# Stratologger_sl100_Board.net
KiCad netlist of a schematic drawn in EAGLE
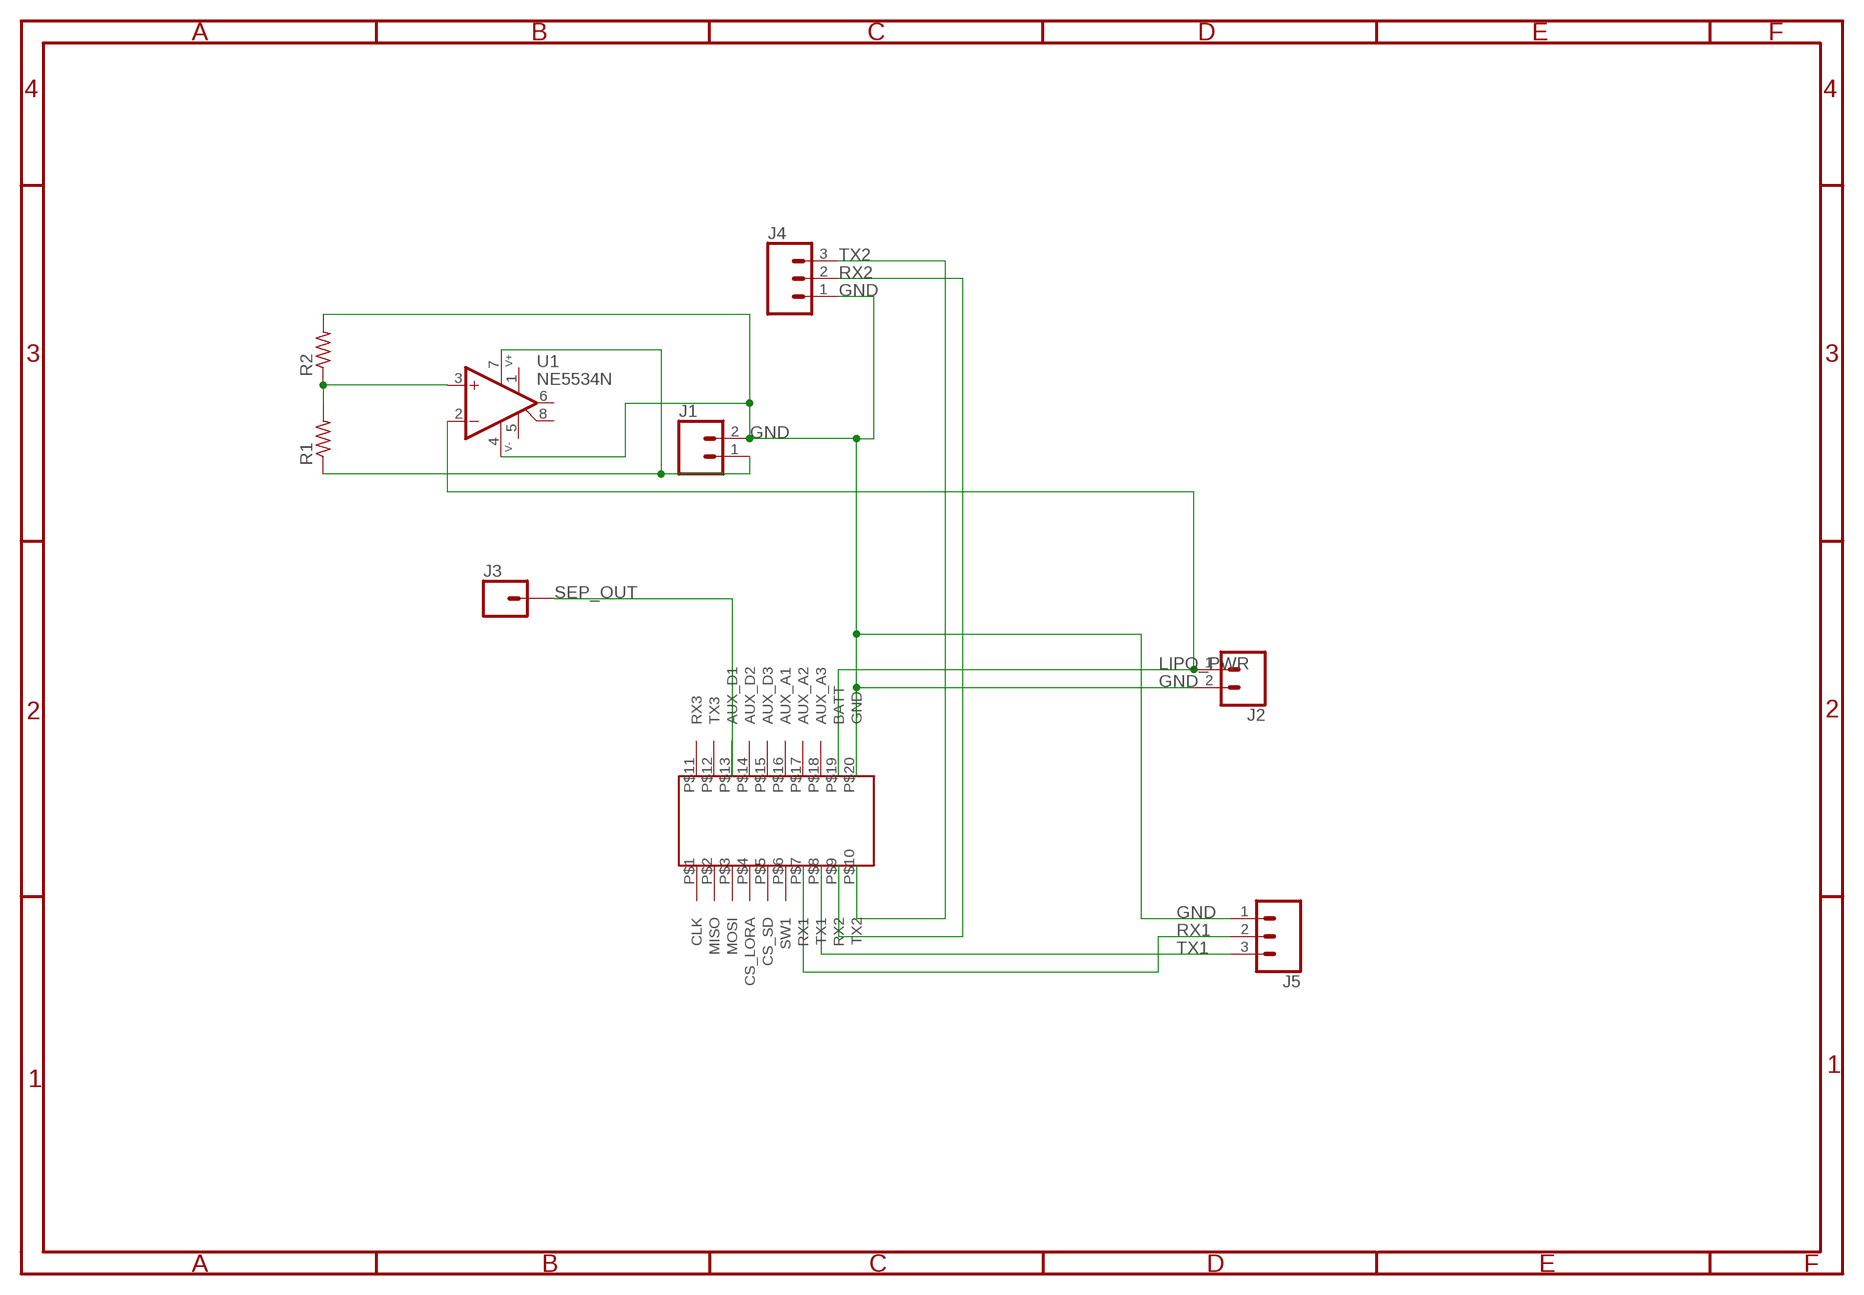
[diagram p0: schematic, sheet 1]

(export (version "E")
  (design (tool "Eeschema 10.0.6"))
  (components
    (comp (ref "J1")
      (value "CONN_02")
      (footprint "eagle-import:1X02")
      (libsource (lib "eagle-import") (part "CONN_02"))
    )
    (comp (ref "J2")
      (value "CONN_02")
      (footprint "eagle-import:1X02")
      (libsource (lib "eagle-import") (part "CONN_02"))
    )
    (comp (ref "J3")
      (value "CONN_01")
      (footprint "eagle-import:1X01")
      (libsource (lib "eagle-import") (part "CONN_01"))
    )
    (comp (ref "J4")
      (value "CONN_03")
      (footprint "eagle-import:1X03")
      (libsource (lib "eagle-import") (part "CONN_03"))
    )
    (comp (ref "J5")
      (value "CONN_03")
      (footprint "eagle-import:1X03")
      (libsource (lib "eagle-import") (part "CONN_03"))
    )
    (comp (ref "R1")
      (value "R-US_0207/12")
      (footprint "eagle-import:0207_12")
      (libsource (lib "eagle-import") (part "R-US_0207/12"))
    )
    (comp (ref "R2")
      (value "R-US_0207/12")
      (footprint "eagle-import:0207_12")
      (libsource (lib "eagle-import") (part "R-US_0207/12"))
    )
    (comp (ref "U$2")
      (value "STRATOLOGGER")
      (footprint "eagle-import:STRATOLOGGER")
      (libsource (lib "eagle-import") (part "STRATOLOGGER"))
    )
    (comp (ref "U$3")
      (value "SMALLHEADERPACKAGE")
      (footprint "eagle-import:SMALLHEADERPACKAGE")
      (libsource (lib "eagle-import") (part "SMALLHEADERPACKAGE"))
    )
    (comp (ref "U1")
      (value "NE5534N")
      (footprint "eagle-import:DIL08")
      (libsource (lib "eagle-import") (part "NE5534N"))
    )
  )
  (nets
    (net (code "1") (name "/GND") (class "Default")
      (node (ref "J1") (pin "2") (pinfunction "2_2") (pintype "passive"))
      (node (ref "J2") (pin "2") (pinfunction "2_2") (pintype "passive"))
      (node (ref "J4") (pin "1") (pinfunction "1_1") (pintype "passive"))
      (node (ref "J5") (pin "1") (pinfunction "1_1") (pintype "passive"))
      (node (ref "R2") (pin "2") (pinfunction "2_2") (pintype "passive"))
      (node (ref "U$3") (pin "P$20") (pinfunction "GND_P$20") (pintype "bidirectional"))
      (node (ref "U1") (pin "4") (pinfunction "V-_4") (pintype "power_in"))
    )
    (net (code "2") (name "/LIPO_PWR") (class "Default")
      (node (ref "J2") (pin "1") (pinfunction "1_1") (pintype "passive"))
      (node (ref "U$3") (pin "P$19") (pinfunction "BATT_P$19") (pintype "bidirectional"))
      (node (ref "U1") (pin "2") (pinfunction "-IN_2") (pintype "input"))
    )
    (net (code "3") (name "/RX1") (class "Default")
      (node (ref "J5") (pin "2") (pinfunction "2_2") (pintype "passive"))
      (node (ref "U$3") (pin "P$7") (pinfunction "RX1_P$7") (pintype "bidirectional"))
    )
    (net (code "4") (name "/RX2") (class "Default")
      (node (ref "J4") (pin "2") (pinfunction "2_2") (pintype "passive"))
      (node (ref "U$3") (pin "P$9") (pinfunction "RX2_P$9") (pintype "bidirectional"))
    )
    (net (code "5") (name "/SEP_OUT") (class "Default")
      (node (ref "J3") (pin "1") (pinfunction "1_1") (pintype "passive"))
      (node (ref "U$3") (pin "P$13") (pinfunction "AUX_D1_P$13") (pintype "bidirectional"))
    )
    (net (code "6") (name "/TX1") (class "Default")
      (node (ref "J5") (pin "3") (pinfunction "3_3") (pintype "passive"))
      (node (ref "U$3") (pin "P$8") (pinfunction "TX1_P$8") (pintype "bidirectional"))
    )
    (net (code "7") (name "/TX2") (class "Default")
      (node (ref "J4") (pin "3") (pinfunction "3_3") (pintype "passive"))
      (node (ref "U$3") (pin "P$10") (pinfunction "TX2_P$10") (pintype "bidirectional"))
    )
    (net (code "8") (name "Net-(U1C-+IN)") (class "Default")
      (node (ref "R1") (pin "2") (pinfunction "2_2") (pintype "passive"))
      (node (ref "R2") (pin "1") (pinfunction "1_1") (pintype "passive"))
      (node (ref "U1") (pin "3") (pinfunction "+IN_3") (pintype "input"))
    )
    (net (code "9") (name "Net-(U1D-V+)") (class "Default")
      (node (ref "J1") (pin "1") (pinfunction "1_1") (pintype "passive"))
      (node (ref "R1") (pin "1") (pinfunction "1_1") (pintype "passive"))
      (node (ref "U1") (pin "7") (pinfunction "V+_7") (pintype "power_in"))
    )
    (net (code "10") (name "unconnected-(U$3-AUX_A1-PadP$16)") (class "Default")
      (node (ref "U$3") (pin "P$16") (pinfunction "AUX_A1_P$16") (pintype "bidirectional"))
    )
    (net (code "11") (name "unconnected-(U$3-AUX_A2-PadP$17)") (class "Default")
      (node (ref "U$3") (pin "P$17") (pinfunction "AUX_A2_P$17") (pintype "bidirectional"))
    )
    (net (code "12") (name "unconnected-(U$3-AUX_A3-PadP$18)") (class "Default")
      (node (ref "U$3") (pin "P$18") (pinfunction "AUX_A3_P$18") (pintype "bidirectional"))
    )
    (net (code "13") (name "unconnected-(U$3-AUX_D2-PadP$14)") (class "Default")
      (node (ref "U$3") (pin "P$14") (pinfunction "AUX_D2_P$14") (pintype "bidirectional"))
    )
    (net (code "14") (name "unconnected-(U$3-AUX_D3-PadP$15)") (class "Default")
      (node (ref "U$3") (pin "P$15") (pinfunction "AUX_D3_P$15") (pintype "bidirectional"))
    )
    (net (code "15") (name "unconnected-(U$3-CLK-PadP$1)") (class "Default")
      (node (ref "U$3") (pin "P$1") (pinfunction "CLK_P$1") (pintype "bidirectional"))
    )
    (net (code "16") (name "unconnected-(U$3-CS_LORA-PadP$4)") (class "Default")
      (node (ref "U$3") (pin "P$4") (pinfunction "CS_LORA_P$4") (pintype "bidirectional"))
    )
    (net (code "17") (name "unconnected-(U$3-CS_SD-PadP$5)") (class "Default")
      (node (ref "U$3") (pin "P$5") (pinfunction "CS_SD_P$5") (pintype "bidirectional"))
    )
    (net (code "18") (name "unconnected-(U$3-MISO-PadP$2)") (class "Default")
      (node (ref "U$3") (pin "P$2") (pinfunction "MISO_P$2") (pintype "bidirectional"))
    )
    (net (code "19") (name "unconnected-(U$3-MOSI-PadP$3)") (class "Default")
      (node (ref "U$3") (pin "P$3") (pinfunction "MOSI_P$3") (pintype "bidirectional"))
    )
    (net (code "20") (name "unconnected-(U$3-RX3-PadP$11)") (class "Default")
      (node (ref "U$3") (pin "P$11") (pinfunction "RX3_P$11") (pintype "bidirectional"))
    )
    (net (code "21") (name "unconnected-(U$3-SW1-PadP$6)") (class "Default")
      (node (ref "U$3") (pin "P$6") (pinfunction "SW1_P$6") (pintype "bidirectional"))
    )
    (net (code "22") (name "unconnected-(U$3-TX3-PadP$12)") (class "Default")
      (node (ref "U$3") (pin "P$12") (pinfunction "TX3_P$12") (pintype "bidirectional"))
    )
    (net (code "23") (name "unconnected-(U1A-BAL-Pad1)") (class "Default")
      (node (ref "U1") (pin "1") (pinfunction "BAL_1") (pintype "passive"))
    )
    (net (code "24") (name "unconnected-(U1B-BAL{slash}CMP-Pad8)") (class "Default")
      (node (ref "U1") (pin "8") (pinfunction "BAL/CMP_8") (pintype "passive"))
    )
    (net (code "25") (name "unconnected-(U1B-CMP-Pad5)") (class "Default")
      (node (ref "U1") (pin "5") (pinfunction "CMP_5") (pintype "passive"))
    )
    (net (code "26") (name "unconnected-(U1C-OUT-Pad6)") (class "Default")
      (node (ref "U1") (pin "6") (pinfunction "OUT_6") (pintype "output"))
    )
  )
)
